# LB_BIT_o1_LED.net
KiCad netlist of a schematic drawn in EAGLE
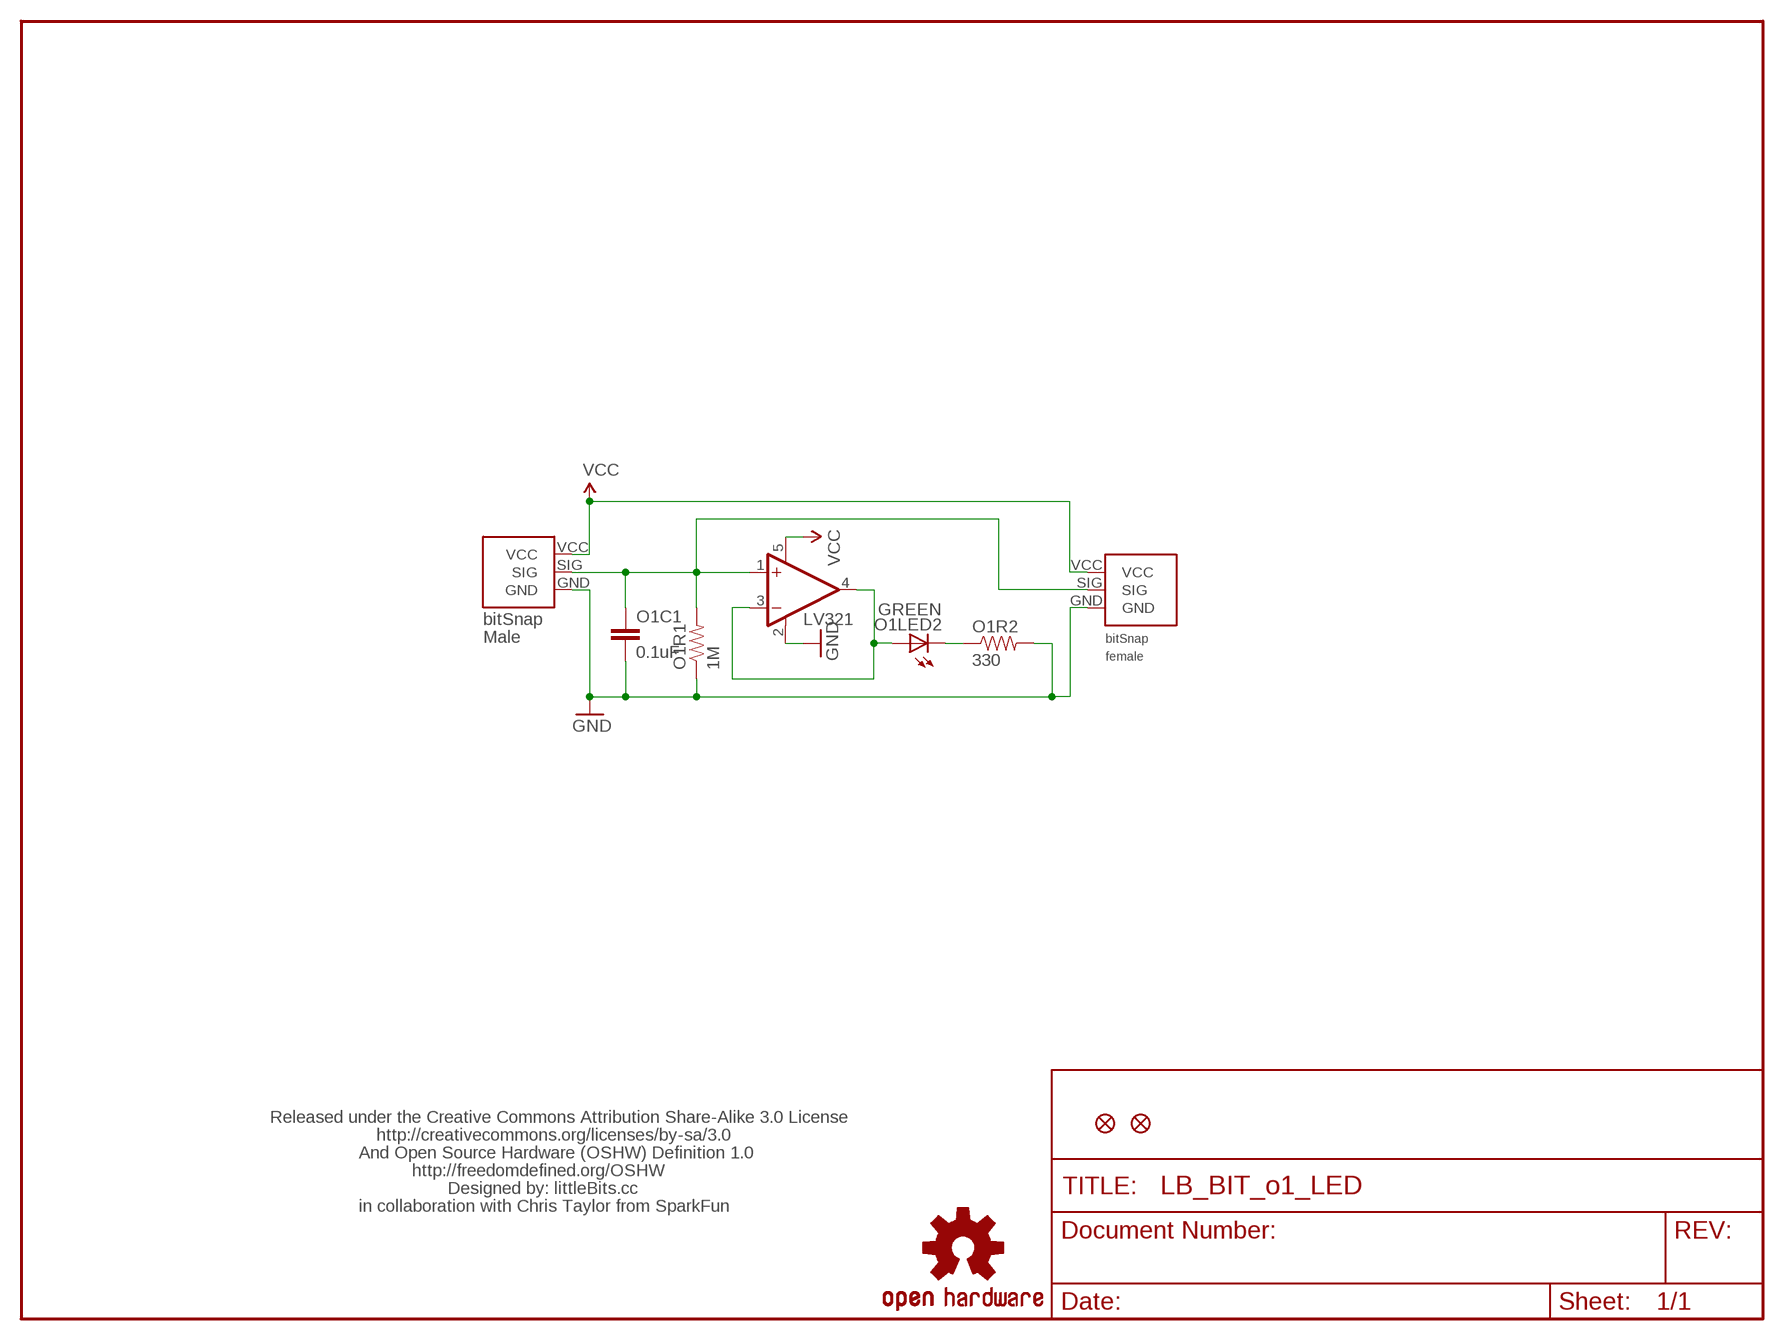
[diagram p0: schematic, sheet 1]

(export (version "E")
  (design (tool "Eeschema 10.0.6"))
  (components
    (comp (ref "JP1")
      (value "FIDUCIAL1X2.5")
      (footprint "eagle-import:FIDUCIAL-1X2.5")
      (libsource (lib "eagle-import") (part "FIDUCIAL1X2.5"))
    )
    (comp (ref "JP2")
      (value "FIDUCIAL1X2.5")
      (footprint "eagle-import:FIDUCIAL-1X2.5")
      (libsource (lib "eagle-import") (part "FIDUCIAL1X2.5"))
    )
    (comp (ref "O1BSF")
      (value "BITSNAP_FEMALE")
      (footprint "eagle-import:BITSNAP_FEMALE")
      (libsource (lib "eagle-import") (part "BITSNAP_FEMALE"))
    )
    (comp (ref "O1BSM")
      (value "BITSNAP_MALE")
      (footprint "eagle-import:BITSNAP_MALE")
      (libsource (lib "eagle-import") (part "BITSNAP_MALE"))
    )
    (comp (ref "O1C1")
      (value "0.1uF")
      (footprint "eagle-import:0603-CAP")
      (libsource (lib "eagle-import") (part "CAP0603-CAP"))
    )
    (comp (ref "O1LED2")
      (value "GREEN")
      (footprint "eagle-import:LED-1206")
      (libsource (lib "eagle-import") (part "LED1206"))
    )
    (comp (ref "O1R1")
      (value "1M")
      (footprint "eagle-import:0603-RES")
      (libsource (lib "eagle-import") (part "RESISTOR0603-RES"))
    )
    (comp (ref "O1R2")
      (value "330")
      (footprint "eagle-import:0603-RES")
      (libsource (lib "eagle-import") (part "RESISTOR0603-RES"))
    )
    (comp (ref "O1U1")
      (value "LV321")
      (footprint "eagle-import:SC70")
      (libsource (lib "eagle-import") (part "LV321"))
    )
    (comp (ref "U$1")
      (value "LB_CREDITS")
      (footprint "eagle-import:OSHWCREDIT")
      (libsource (lib "eagle-import") (part "LB_CREDITS"))
    )
    (comp (ref "U$3")
      (value "OSHW-LOGOL")
      (footprint "eagle-import:OSHW-LOGO-L")
      (libsource (lib "eagle-import") (part "OSHW-LOGOL"))
    )
  )
  (nets
    (net (code "1") (name "GND") (class "Default")
      (node (ref "O1BSF") (pin "GND") (pinfunction "GND_GND") (pintype "bidirectional"))
      (node (ref "O1BSM") (pin "GND") (pinfunction "GND_GND") (pintype "bidirectional"))
      (node (ref "O1C1") (pin "2") (pinfunction "2_2") (pintype "passive"))
      (node (ref "O1R1") (pin "1") (pinfunction "1_1") (pintype "passive"))
      (node (ref "O1R2") (pin "2") (pinfunction "2_2") (pintype "passive"))
      (node (ref "O1U1") (pin "2") (pinfunction "V-_2") (pintype "power_in"))
    )
    (net (code "2") (name "Net-(O1LED2-PadC)") (class "Default")
      (node (ref "O1LED2") (pin "C") (pinfunction "C_C") (pintype "passive"))
      (node (ref "O1R2") (pin "1") (pinfunction "1_1") (pintype "passive"))
    )
    (net (code "3") (name "Net-(O1U1-+IN)") (class "Default")
      (node (ref "O1BSF") (pin "SIG") (pinfunction "SIG_SIG") (pintype "bidirectional"))
      (node (ref "O1BSM") (pin "SIG") (pinfunction "SIG_SIG") (pintype "bidirectional"))
      (node (ref "O1C1") (pin "1") (pinfunction "1_1") (pintype "passive"))
      (node (ref "O1R1") (pin "2") (pinfunction "2_2") (pintype "passive"))
      (node (ref "O1U1") (pin "1") (pinfunction "+IN_1") (pintype "input"))
    )
    (net (code "4") (name "Net-(O1U1--IN)") (class "Default")
      (node (ref "O1LED2") (pin "A") (pinfunction "A_A") (pintype "passive"))
      (node (ref "O1U1") (pin "3") (pinfunction "-IN_3") (pintype "input"))
      (node (ref "O1U1") (pin "4") (pinfunction "OUT_4") (pintype "output"))
    )
    (net (code "5") (name "VCC") (class "Default")
      (node (ref "O1BSF") (pin "VCC") (pinfunction "VCC_VCC") (pintype "bidirectional"))
      (node (ref "O1BSM") (pin "VCC") (pinfunction "VCC_VCC") (pintype "bidirectional"))
      (node (ref "O1U1") (pin "5") (pinfunction "V+_5") (pintype "power_in"))
    )
  )
)
